# CC2530.net
KiCad netlist of a schematic drawn in Altium Designer
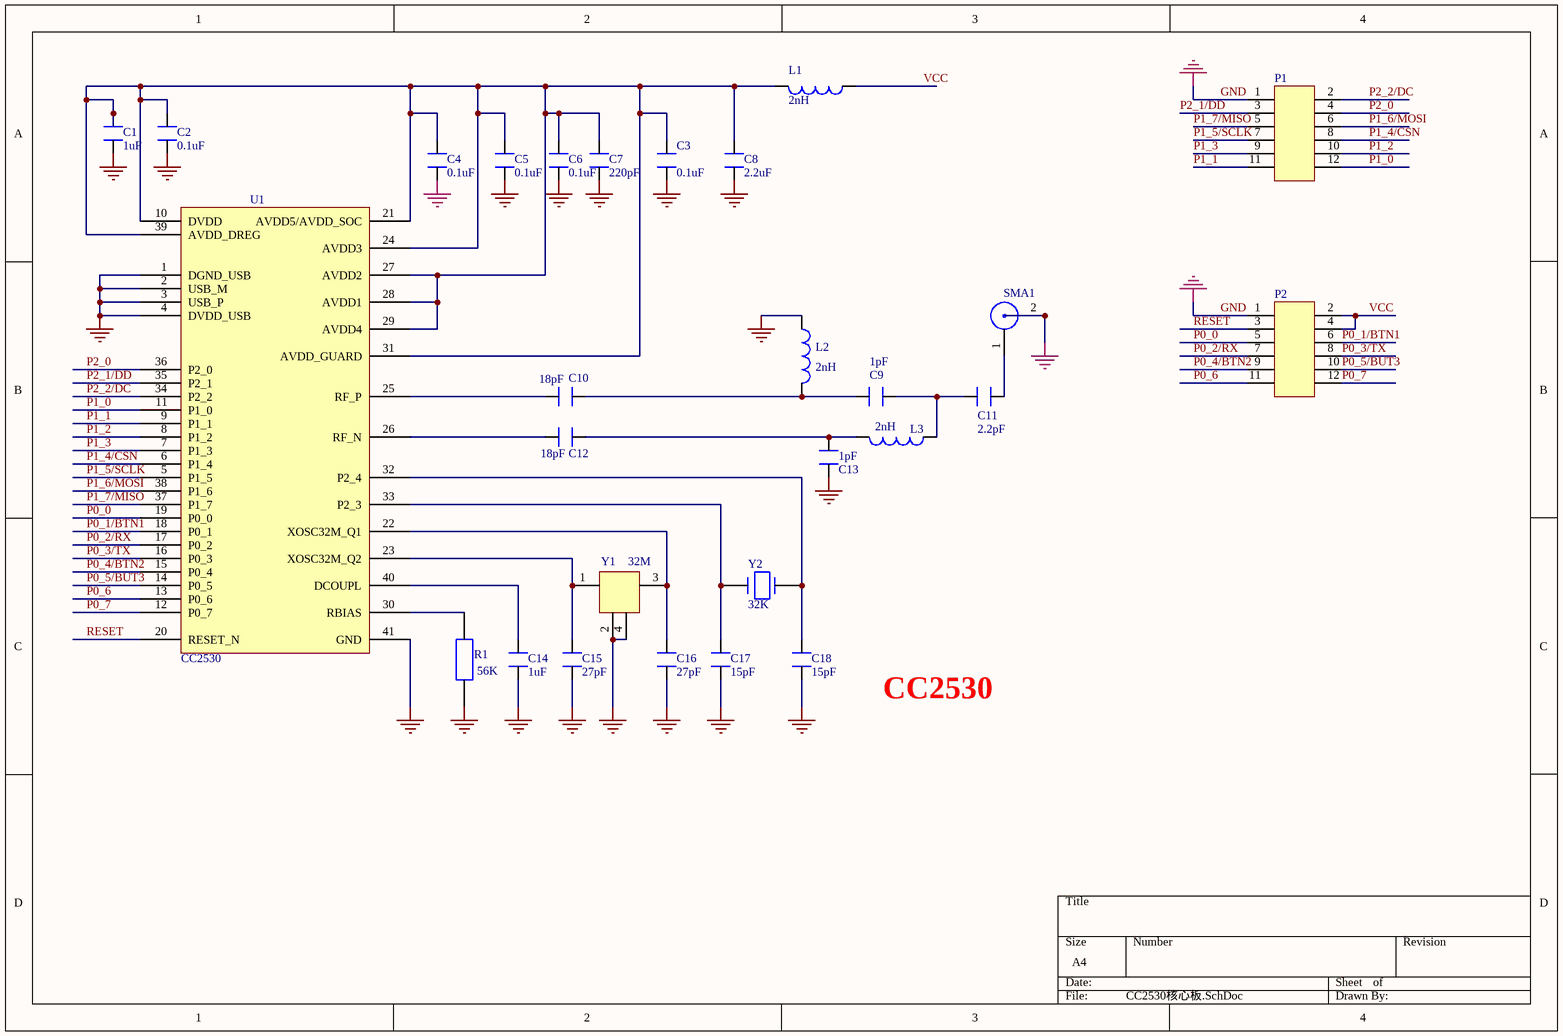
[diagram p0: CC2530核心板.SchDoc]

(export (version "E")
  (design (tool "Eeschema 10.0.6"))
  (components
    (comp (ref "C1") (value "1uF") (footprint "C 0603_L") (libsource (lib "*") (part "C")))
    (comp (ref "C2") (value "0.1uF") (footprint "C 0603_L") (libsource (lib "*") (part "C")))
    (comp (ref "C3") (value "0.1uF") (footprint "C 0603_L") (libsource (lib "*") (part "C")))
    (comp (ref "C4") (value "0.1uF") (footprint "C 0603_L") (libsource (lib "*") (part "C")))
    (comp (ref "C5") (value "0.1uF") (footprint "C 0603_L") (libsource (lib "*") (part "C")))
    (comp (ref "C6") (value "0.1uF") (footprint "C 0603_L") (libsource (lib "*") (part "C")))
    (comp (ref "C7") (value "220pF") (footprint "C 0603_L") (libsource (lib "*") (part "C")))
    (comp (ref "C8") (value "2.2uF") (footprint "C 0603_L") (libsource (lib "*") (part "C")))
    (comp (ref "C9") (value "1pF") (footprint "C 0603_L") (libsource (lib "*") (part "C")))
    (comp (ref "C10") (value "18pF") (footprint "C 0603_L") (libsource (lib "*") (part "C")))
    (comp (ref "C11") (value "2.2pF") (footprint "C 0603_L") (libsource (lib "*") (part "C")))
    (comp (ref "C12") (value "18pF") (footprint "C 0603_L") (libsource (lib "*") (part "C")))
    (comp (ref "C13") (value "1pF") (footprint "C 0603_L") (libsource (lib "*") (part "C")))
    (comp (ref "C14") (value "1uF") (footprint "C 0603_L") (libsource (lib "*") (part "C")))
    (comp (ref "C15") (value "27pF") (footprint "C 0603_L") (libsource (lib "*") (part "C")))
    (comp (ref "C16") (value "27pF") (footprint "C 0603_L") (libsource (lib "*") (part "C")))
    (comp (ref "C17") (value "15pF") (footprint "C 0603_L") (libsource (lib "*") (part "C")))
    (comp (ref "C18") (value "15pF") (footprint "C 0603_L") (libsource (lib "*") (part "C")))
    (comp (ref "L1") (value "2nH") (footprint "L 0603") (libsource (lib "*") (part "L")))
    (comp (ref "L2") (value "2nH") (footprint "L 0603") (libsource (lib "") (part "L_1")))
    (comp (ref "L3") (value "2nH") (footprint "L 0603") (libsource (lib "*") (part "L")))
    (comp (ref "P1") (value "~") (footprint "HDR2.54-LI-2x6P") (libsource (lib "*") (part "CON12")))
    (comp (ref "P2") (value "~") (footprint "HDR2.54-LI-2x6P") (libsource (lib "*") (part "CON12")))
    (comp (ref "R1") (value "56K") (footprint "R 0603-HP_L") (libsource (lib "*") (part "R")))
    (comp (ref "SMA1") (value "~") (footprint "SMA-KE") (libsource (lib "*") (part "SMA")))
    (comp (ref "U1") (value "CC2530") (footprint "QFN40") (libsource (lib "cc2530节点") (part "CC2530")))
    (comp (ref "Y1") (value "32M") (footprint "OSC 3225-4P") (libsource (lib "*") (part "32M")))
    (comp (ref "Y2") (value "32K") (footprint "OSC 3215-2P") (libsource (lib "*") (part "32K")))
  )
  (nets
    (net (code "1") (name "/P0_0") (class "Default")
      (node (ref "P2") (pin "5") (pinfunction "5_5") (pintype "passive"))
      (node (ref "U1") (pin "19") (pinfunction "P0_0_19") (pintype "passive"))
    )
    (net (code "2") (name "/P0_1{slash}BTN1") (class "Default")
      (node (ref "P2") (pin "6") (pinfunction "6_6") (pintype "passive"))
      (node (ref "U1") (pin "18") (pinfunction "P0_1_18") (pintype "passive"))
    )
    (net (code "3") (name "/P0_2{slash}RX") (class "Default")
      (node (ref "P2") (pin "7") (pinfunction "7_7") (pintype "passive"))
      (node (ref "U1") (pin "17") (pinfunction "P0_2_17") (pintype "passive"))
    )
    (net (code "4") (name "/P0_3{slash}TX") (class "Default")
      (node (ref "P2") (pin "8") (pinfunction "8_8") (pintype "passive"))
      (node (ref "U1") (pin "16") (pinfunction "P0_3_16") (pintype "passive"))
    )
    (net (code "5") (name "/P0_4{slash}BTN2") (class "Default")
      (node (ref "P2") (pin "9") (pinfunction "9_9") (pintype "passive"))
      (node (ref "U1") (pin "15") (pinfunction "P0_4_15") (pintype "passive"))
    )
    (net (code "6") (name "/P0_5{slash}BUT3") (class "Default")
      (node (ref "P2") (pin "10") (pinfunction "10_10") (pintype "passive"))
      (node (ref "U1") (pin "14") (pinfunction "P0_5_14") (pintype "passive"))
    )
    (net (code "7") (name "/P0_6") (class "Default")
      (node (ref "P2") (pin "11") (pinfunction "11_11") (pintype "passive"))
      (node (ref "U1") (pin "13") (pinfunction "P0_6_13") (pintype "passive"))
    )
    (net (code "8") (name "/P0_7") (class "Default")
      (node (ref "P2") (pin "12") (pinfunction "12_12") (pintype "passive"))
      (node (ref "U1") (pin "12") (pinfunction "P0_7_12") (pintype "passive"))
    )
    (net (code "9") (name "/P1_0") (class "Default")
      (node (ref "P1") (pin "12") (pinfunction "12_12") (pintype "passive"))
      (node (ref "U1") (pin "11") (pinfunction "P1_0_11") (pintype "passive"))
    )
    (net (code "10") (name "/P1_1") (class "Default")
      (node (ref "P1") (pin "11") (pinfunction "11_11") (pintype "passive"))
      (node (ref "U1") (pin "9") (pinfunction "P1_1_9") (pintype "passive"))
    )
    (net (code "11") (name "/P1_2") (class "Default")
      (node (ref "P1") (pin "10") (pinfunction "10_10") (pintype "passive"))
      (node (ref "U1") (pin "8") (pinfunction "P1_2_8") (pintype "passive"))
    )
    (net (code "12") (name "/P1_3") (class "Default")
      (node (ref "P1") (pin "9") (pinfunction "9_9") (pintype "passive"))
      (node (ref "U1") (pin "7") (pinfunction "P1_3_7") (pintype "passive"))
    )
    (net (code "13") (name "/P1_4{slash}CSN") (class "Default")
      (node (ref "P1") (pin "8") (pinfunction "8_8") (pintype "passive"))
      (node (ref "U1") (pin "6") (pinfunction "P1_4_6") (pintype "passive"))
    )
    (net (code "14") (name "/P1_5{slash}SCLK") (class "Default")
      (node (ref "P1") (pin "7") (pinfunction "7_7") (pintype "passive"))
      (node (ref "U1") (pin "5") (pinfunction "P1_5_5") (pintype "passive"))
    )
    (net (code "15") (name "/P1_6{slash}MOSI") (class "Default")
      (node (ref "P1") (pin "6") (pinfunction "6_6") (pintype "passive"))
      (node (ref "U1") (pin "38") (pinfunction "P1_6_38") (pintype "passive"))
    )
    (net (code "16") (name "/P1_7{slash}MISO") (class "Default")
      (node (ref "P1") (pin "5") (pinfunction "5_5") (pintype "passive"))
      (node (ref "U1") (pin "37") (pinfunction "P1_7_37") (pintype "passive"))
    )
    (net (code "17") (name "/P2_0") (class "Default")
      (node (ref "P1") (pin "4") (pinfunction "4_4") (pintype "passive"))
      (node (ref "U1") (pin "36") (pinfunction "P2_0_36") (pintype "passive"))
    )
    (net (code "18") (name "/P2_1{slash}DD") (class "Default")
      (node (ref "P1") (pin "3") (pinfunction "3_3") (pintype "passive"))
      (node (ref "U1") (pin "35") (pinfunction "P2_1_35") (pintype "passive"))
    )
    (net (code "19") (name "/P2_2{slash}DC") (class "Default")
      (node (ref "P1") (pin "2") (pinfunction "2_2") (pintype "passive"))
      (node (ref "U1") (pin "34") (pinfunction "P2_2_34") (pintype "passive"))
    )
    (net (code "20") (name "/RESET") (class "Default")
      (node (ref "P2") (pin "3") (pinfunction "3_3") (pintype "passive"))
      (node (ref "U1") (pin "20") (pinfunction "RESET_N_20") (pintype "passive"))
    )
    (net (code "21") (name "/VCC") (class "Default")
      (node (ref "L1") (pin "2") (pinfunction "2_2") (pintype "passive"))
      (node (ref "P2") (pin "2") (pinfunction "2_2") (pintype "passive"))
      (node (ref "P2") (pin "4") (pinfunction "4_4") (pintype "passive"))
    )
    (net (code "22") (name "GND") (class "Default")
      (node (ref "C1") (pin "1") (pinfunction "1_1") (pintype "passive"))
      (node (ref "C13") (pin "1") (pinfunction "1_1") (pintype "passive"))
      (node (ref "C14") (pin "2") (pinfunction "2_2") (pintype "passive"))
      (node (ref "C15") (pin "1") (pinfunction "1_1") (pintype "passive"))
      (node (ref "C16") (pin "1") (pinfunction "1_1") (pintype "passive"))
      (node (ref "C17") (pin "1") (pinfunction "1_1") (pintype "passive"))
      (node (ref "C18") (pin "1") (pinfunction "1_1") (pintype "passive"))
      (node (ref "C2") (pin "2") (pinfunction "2_2") (pintype "passive"))
      (node (ref "C3") (pin "1") (pinfunction "1_1") (pintype "passive"))
      (node (ref "C4") (pin "1") (pinfunction "1_1") (pintype "passive"))
      (node (ref "C5") (pin "1") (pinfunction "1_1") (pintype "passive"))
      (node (ref "C6") (pin "1") (pinfunction "1_1") (pintype "passive"))
      (node (ref "C7") (pin "1") (pinfunction "1_1") (pintype "passive"))
      (node (ref "C8") (pin "1") (pinfunction "1_1") (pintype "passive"))
      (node (ref "L2") (pin "2") (pinfunction "2_2") (pintype "passive"))
      (node (ref "P1") (pin "1") (pinfunction "1_1") (pintype "passive"))
      (node (ref "P2") (pin "1") (pinfunction "1_1") (pintype "passive"))
      (node (ref "R1") (pin "1") (pinfunction "1_1") (pintype "passive"))
      (node (ref "SMA1") (pin "2") (pinfunction "2_2") (pintype "passive"))
      (node (ref "U1") (pin "1") (pinfunction "DGND_USB_1") (pintype "passive"))
      (node (ref "U1") (pin "2") (pinfunction "USB_M_2") (pintype "passive"))
      (node (ref "U1") (pin "3") (pinfunction "USB_P_3") (pintype "passive"))
      (node (ref "U1") (pin "4") (pinfunction "DVDD_USB_4") (pintype "passive"))
      (node (ref "U1") (pin "41") (pinfunction "GND_41") (pintype "passive"))
      (node (ref "Y1") (pin "2") (pinfunction "2_2") (pintype "passive"))
      (node (ref "Y1") (pin "4") (pinfunction "4_4") (pintype "passive"))
    )
    (net (code "23") (name "Net-(C10-Pad1)") (class "Default")
      (node (ref "C10") (pin "1") (pinfunction "1_1") (pintype "passive"))
      (node (ref "C9") (pin "1") (pinfunction "1_1") (pintype "passive"))
      (node (ref "L2") (pin "1") (pinfunction "1_1") (pintype "passive"))
    )
    (net (code "24") (name "Net-(C11-Pad1)") (class "Default")
      (node (ref "C11") (pin "1") (pinfunction "1_1") (pintype "passive"))
      (node (ref "C9") (pin "2") (pinfunction "2_2") (pintype "passive"))
      (node (ref "L3") (pin "2") (pinfunction "2_2") (pintype "passive"))
    )
    (net (code "25") (name "Net-(C11-Pad2)") (class "Default")
      (node (ref "C11") (pin "2") (pinfunction "2_2") (pintype "passive"))
      (node (ref "SMA1") (pin "1") (pinfunction "1_1") (pintype "passive"))
    )
    (net (code "26") (name "Net-(C12-Pad1)") (class "Default")
      (node (ref "C12") (pin "1") (pinfunction "1_1") (pintype "passive"))
      (node (ref "C13") (pin "2") (pinfunction "2_2") (pintype "passive"))
      (node (ref "L3") (pin "1") (pinfunction "1_1") (pintype "passive"))
    )
    (net (code "27") (name "Net-(U1-AVDD1)") (class "Default")
      (node (ref "C1") (pin "2") (pinfunction "2_2") (pintype "passive"))
      (node (ref "C2") (pin "1") (pinfunction "1_1") (pintype "passive"))
      (node (ref "C3") (pin "2") (pinfunction "2_2") (pintype "passive"))
      (node (ref "C4") (pin "2") (pinfunction "2_2") (pintype "passive"))
      (node (ref "C5") (pin "2") (pinfunction "2_2") (pintype "passive"))
      (node (ref "C6") (pin "2") (pinfunction "2_2") (pintype "passive"))
      (node (ref "C7") (pin "2") (pinfunction "2_2") (pintype "passive"))
      (node (ref "C8") (pin "2") (pinfunction "2_2") (pintype "passive"))
      (node (ref "L1") (pin "1") (pinfunction "1_1") (pintype "passive"))
      (node (ref "U1") (pin "10") (pinfunction "DVDD_10") (pintype "passive"))
      (node (ref "U1") (pin "21") (pinfunction "AVDD5/AVDD_SOC_21") (pintype "passive"))
      (node (ref "U1") (pin "24") (pinfunction "AVDD3_24") (pintype "passive"))
      (node (ref "U1") (pin "27") (pinfunction "AVDD2_27") (pintype "passive"))
      (node (ref "U1") (pin "28") (pinfunction "AVDD1_28") (pintype "passive"))
      (node (ref "U1") (pin "29") (pinfunction "AVDD4_29") (pintype "passive"))
      (node (ref "U1") (pin "31") (pinfunction "AVDD_GUARD_31") (pintype "passive"))
      (node (ref "U1") (pin "39") (pinfunction "AVDD_DREG_39") (pintype "passive"))
    )
    (net (code "28") (name "Net-(U1-DCOUPL)") (class "Default")
      (node (ref "C14") (pin "1") (pinfunction "1_1") (pintype "passive"))
      (node (ref "U1") (pin "40") (pinfunction "DCOUPL_40") (pintype "passive"))
    )
    (net (code "29") (name "Net-(U1-P2_3)") (class "Default")
      (node (ref "C17") (pin "2") (pinfunction "2_2") (pintype "passive"))
      (node (ref "U1") (pin "33") (pinfunction "P2_3_33") (pintype "passive"))
      (node (ref "Y2") (pin "1") (pinfunction "1_1") (pintype "passive"))
    )
    (net (code "30") (name "Net-(U1-P2_4)") (class "Default")
      (node (ref "C18") (pin "2") (pinfunction "2_2") (pintype "passive"))
      (node (ref "U1") (pin "32") (pinfunction "P2_4_32") (pintype "passive"))
      (node (ref "Y2") (pin "2") (pinfunction "2_2") (pintype "passive"))
    )
    (net (code "31") (name "Net-(U1-RBIAS)") (class "Default")
      (node (ref "R1") (pin "2") (pinfunction "2_2") (pintype "passive"))
      (node (ref "U1") (pin "30") (pinfunction "RBIAS_30") (pintype "passive"))
    )
    (net (code "32") (name "Net-(U1-RF_N)") (class "Default")
      (node (ref "C12") (pin "2") (pinfunction "2_2") (pintype "passive"))
      (node (ref "U1") (pin "26") (pinfunction "RF_N_26") (pintype "passive"))
    )
    (net (code "33") (name "Net-(U1-RF_P)") (class "Default")
      (node (ref "C10") (pin "2") (pinfunction "2_2") (pintype "passive"))
      (node (ref "U1") (pin "25") (pinfunction "RF_P_25") (pintype "passive"))
    )
    (net (code "34") (name "Net-(U1-XOSC32M_Q1)") (class "Default")
      (node (ref "C16") (pin "2") (pinfunction "2_2") (pintype "passive"))
      (node (ref "U1") (pin "22") (pinfunction "XOSC32M_Q1_22") (pintype "passive"))
      (node (ref "Y1") (pin "3") (pinfunction "3_3") (pintype "passive"))
    )
    (net (code "35") (name "Net-(U1-XOSC32M_Q2)") (class "Default")
      (node (ref "C15") (pin "2") (pinfunction "2_2") (pintype "passive"))
      (node (ref "U1") (pin "23") (pinfunction "XOSC32M_Q2_23") (pintype "passive"))
      (node (ref "Y1") (pin "1") (pinfunction "1_1") (pintype "passive"))
    )
  )
)
